# Power_Management.net
KiCad netlist of a schematic drawn in Altium Designer
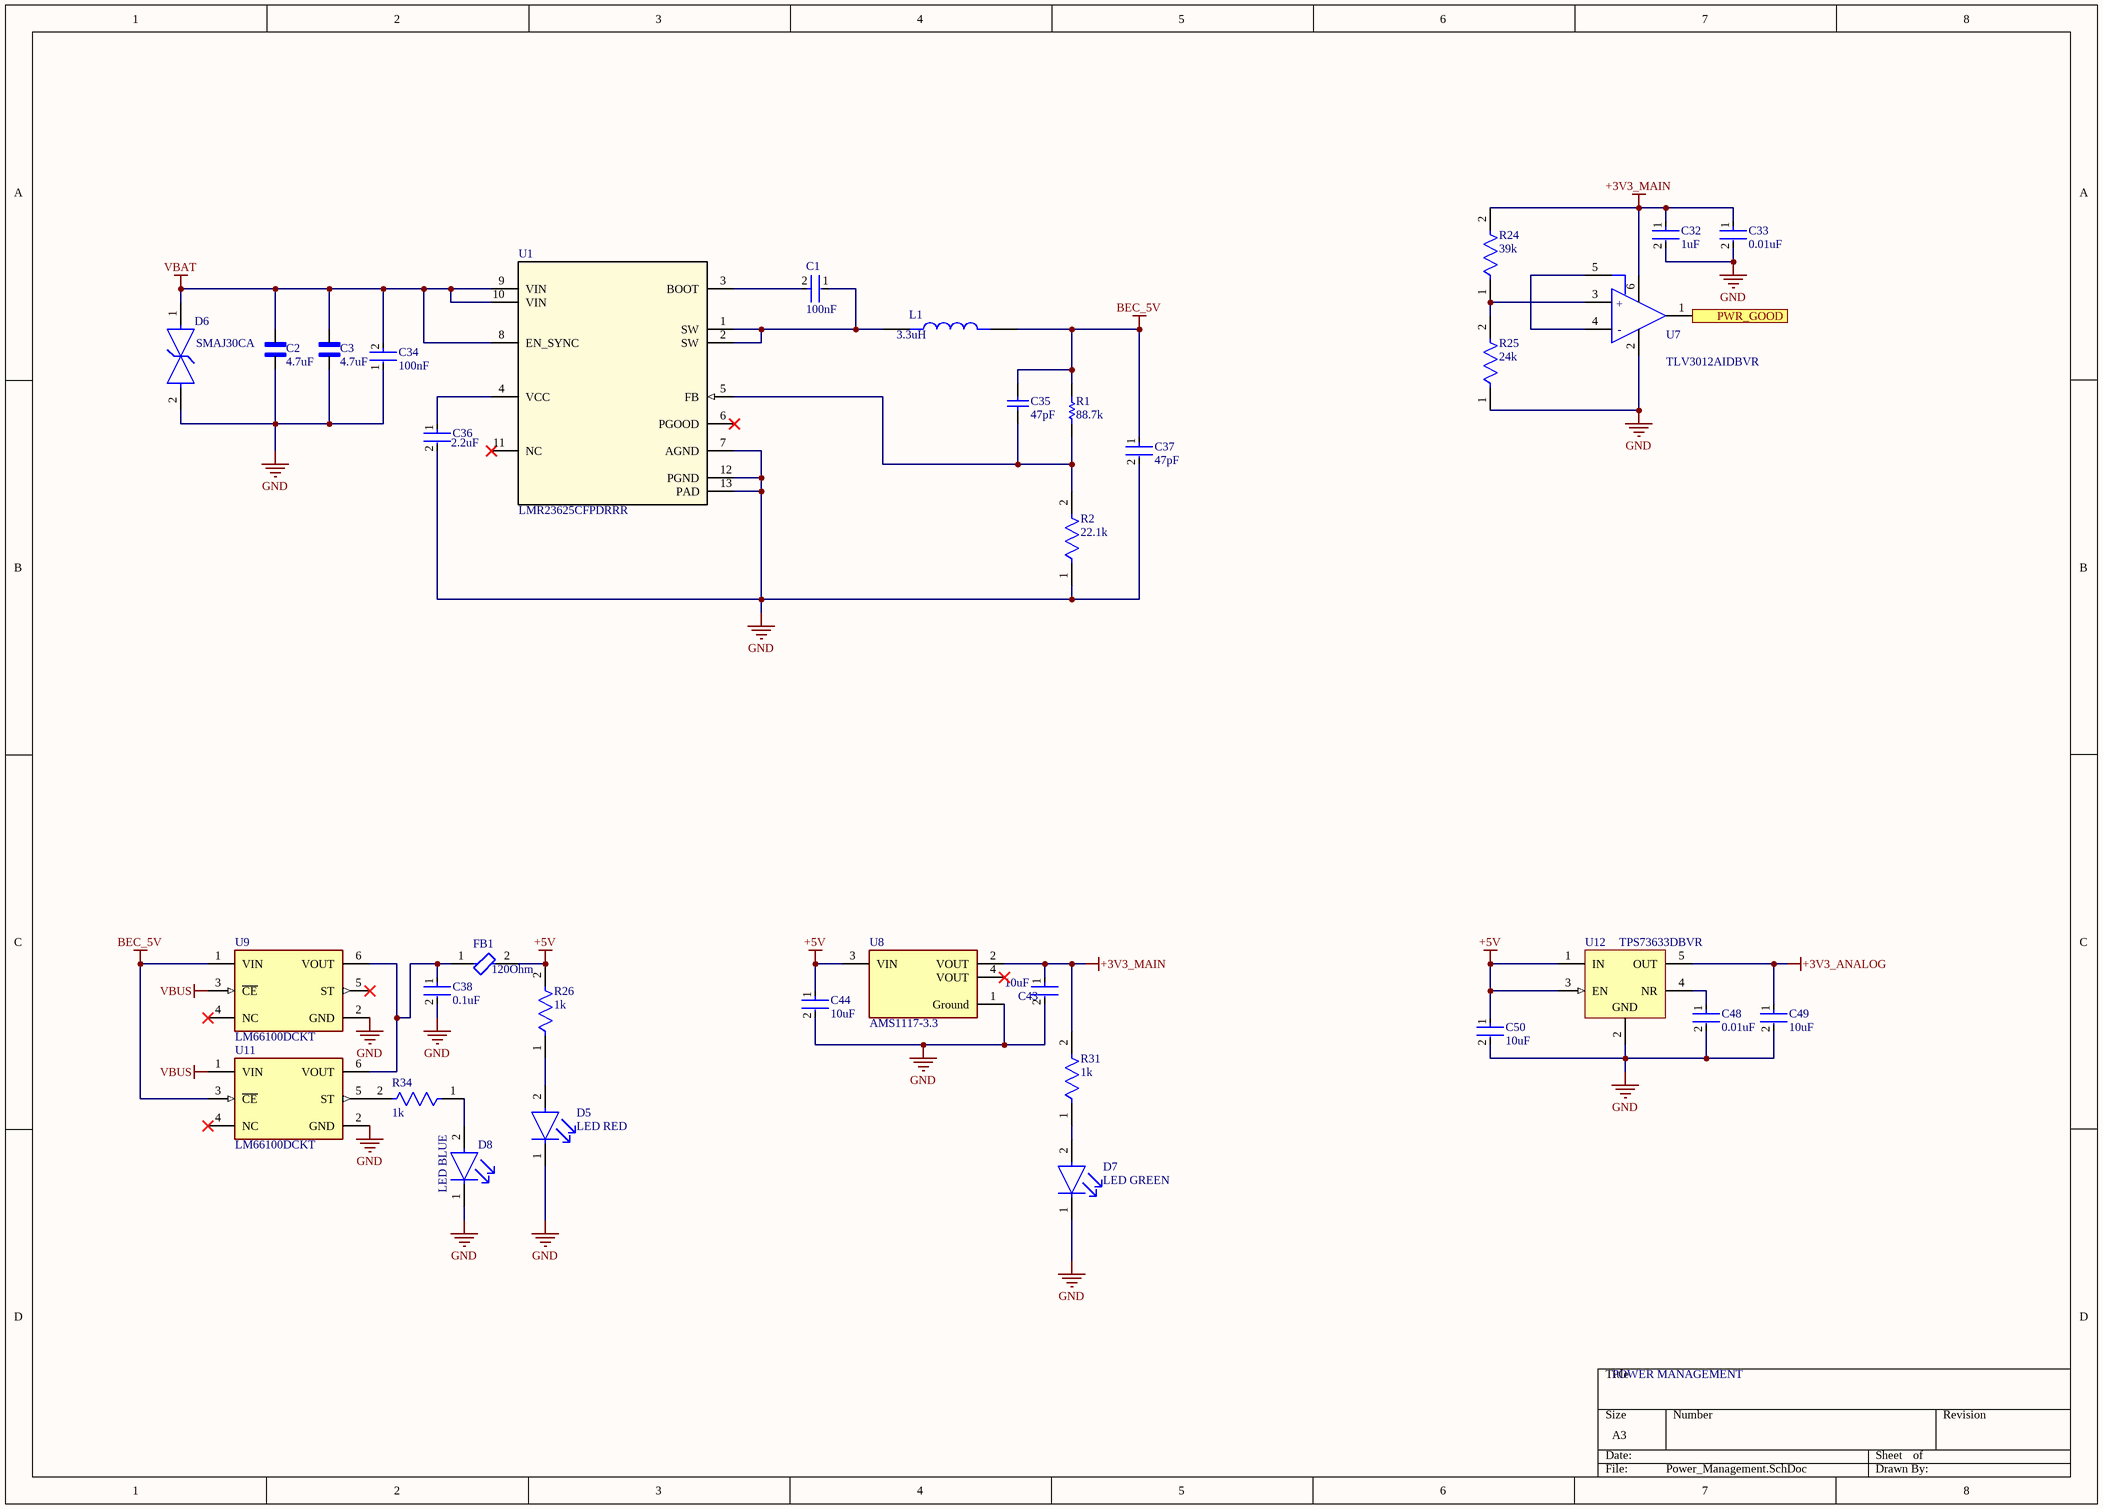
[diagram p0: Power_Management.SchDoc]

(export (version "E")
  (design (tool "Eeschema 10.0.6"))
  (components
    (comp (ref "C1")
      (value "100nF")
      (footprint "FP-GRM15-MFG")
      (description "CAP CER 0.1UF 16V X7R 0402")
      (fields (field (name "MANUFACTURER PART NUMBER") "GRM155R71C104KA88D") (field (name "TOLERANCE") "10%"))
      (libsource (lib "Altium Content Vault") (part "236180d848d6139a670b325ea6854c9"))
    )
    (comp (ref "C2")
      (value "4.7uF")
      (footprint "CAPC3225X270N")
      (fields
        (field (name "MF") "{'manufacturer': u'Taiyo Yuden'}")
        (field (name "MP") "MSASU32MSB7475MPNA01")
      )
      (libsource (lib "4.7uF CAP") (part "MSASU32MSB7475MPNA01"))
    )
    (comp (ref "C3")
      (value "4.7uF")
      (footprint "CAPC3225X270N")
      (fields
        (field (name "MF") "{'manufacturer': u'Taiyo Yuden'}")
        (field (name "MP") "MSASU32MSB7475MPNA01")
      )
      (libsource (lib "4.7uF CAP") (part "MSASU32MSB7475MPNA01"))
    )
    (comp (ref "C32")
      (value "1uF")
      (footprint "FP-GRM155-0_05-IPC_C")
      (description "Chip Multilayer Ceramic Capacitors for General Purpose, 0402, 1.0uF, B, 10%, 10%, 25V")
      (fields (field (name "TOLERANCE") "10%"))
      (libsource (lib "Altium Content Vault") (part "02cd4be3c70576c341d710602a673aa"))
    )
    (comp (ref "C33")
      (value "0.01uF")
      (footprint "FP-GRM022-0_02-IPC_B")
      (libsource (lib "Altium Content Vault") (part "b4654b650e69147ec39a6b967a45e02"))
    )
    (comp (ref "C34")
      (value "100nF")
      (footprint "FP-C1608-080-0_1-IPC_A")
      (description "Multilayer Ceramic Capacitors 100nF ±10% 100V X7S SMD 0603")
      (fields (field (name "TOLERANCE") "10%"))
      (libsource (lib "Altium Content Vault") (part "236180d848d6139a670b325ea6854c9"))
    )
    (comp (ref "C35")
      (value "47pF")
      (footprint "CAPC1005X55X25NL05T10")
      (fields (field (name "PART NUMBER") "GRM1555C1E470JA01D") (field (name "MANUFACTURER") "Murata"))
      (libsource (lib "Altium Content Vault") (part "CAP"))
    )
    (comp (ref "C36")
      (value "2.2uF")
      (footprint "FP-C1005-050-0_05-IPC_A")
      (description "Multilayer Ceramic Capacitors 2.2μF ±10% 16V X5R SMD 0402")
      (fields (field (name "TOLERANCE") "10%"))
      (libsource (lib "Altium Content Vault") (part "b4654b650e69147ec39a6b967a45e02"))
    )
    (comp (ref "C37")
      (value "47pF")
      (footprint "FP-GRM31C-0_2-e0_3_0_8-IPC_A")
      (description "Chip Multilayer Ceramic Capacitors for General Purpose, 1206, 47uF, X5R, 15%, 10%, 10V")
      (fields (field (name "TOLERANCE") "10%"))
      (libsource (lib "Altium Content Vault") (part "02cd4be3c70576c341d710602a673aa"))
    )
    (comp (ref "C38")
      (value "0.1uF")
      (footprint "FP-C0402-BB-MFG")
      (description "CAP CER 0.1UF 10V 20% X7R 0402")
      (fields
        (field (name "OCTOPART") "https://octopart.com/c0402c104m8ractu-kemet-9144037")
        (field (name "TOLERANCE") "0.2")
      )
      (libsource (lib "Altium Content Vault") (part "b4654b650e69147ec39a6b967a45e02"))
    )
    (comp (ref "C43")
      (value "10uF")
      (footprint "FP-C0402C106M9PACTU-MFG")
      (description "CAP CER 10UF 6.3V X5R 0402")
      (fields (field (name "TOLERANCE") "20%"))
      (libsource (lib "Altium Content Vault") (part "b4654b650e69147ec39a6b967a45e02"))
    )
    (comp (ref "C44")
      (value "10uF")
      (footprint "FP-C0402C106M9PACTU-MFG")
      (description "CAP CER 10UF 6.3V X5R 0402")
      (fields (field (name "TOLERANCE") "20%"))
      (libsource (lib "Altium Content Vault") (part "b4654b650e69147ec39a6b967a45e02"))
    )
    (comp (ref "C48")
      (value "0.01uF")
      (footprint "FP-GRM022-0_02-IPC_B")
      (libsource (lib "Altium Content Vault") (part "b4654b650e69147ec39a6b967a45e02"))
    )
    (comp (ref "C49")
      (value "10uF")
      (footprint "FP-C0402C106M9PACTU-MFG")
      (description "CAP CER 10UF 6.3V X5R 0402")
      (fields (field (name "TOLERANCE") "20%"))
      (libsource (lib "Altium Content Vault") (part "b4654b650e69147ec39a6b967a45e02"))
    )
    (comp (ref "C50")
      (value "10uF")
      (footprint "FP-C0402C106M9PACTU-MFG")
      (description "CAP CER 10UF 6.3V X5R 0402")
      (fields (field (name "TOLERANCE") "20%"))
      (libsource (lib "Altium Content Vault") (part "b4654b650e69147ec39a6b967a45e02"))
    )
    (comp (ref "D5")
      (value "LED RED")
      (footprint "FP-SML-LXT0805IW-TR-MFG")
      (description "LED RED DIFFUSED SMD")
      (libsource (lib "Altium Content Vault") (part "8706943c75ba83719d021d2fdc84c58"))
    )
    (comp (ref "D6")
      (value "SMAJ30CA")
      (footprint "FP-SMAJ-CA-MFG")
      (description "TVS DIODE 30V 48.4V DO214AC")
      (libsource (lib "Altium Content Vault") (part "876f4347bf90aa6f500f43e3cd03972"))
    )
    (comp (ref "D7")
      (value "LED GREEN")
      (footprint "FP-LTST-C171GKT-MFG")
      (description "LED GREEN CLEAR CHIP SMD")
      (libsource (lib "Altium Content Vault") (part "8706943c75ba83719d021d2fdc84c58"))
    )
    (comp (ref "D8")
      (value "LED BLUE")
      (footprint "FP-LTST-C191TBKT-MFG")
      (description "LED BLUE CLEAR CHIP SMD")
      (libsource (lib "Altium Content Vault") (part "8706943c75ba83719d021d2fdc84c58"))
    )
    (comp (ref "FB1")
      (value "120Ohm")
      (footprint "FP-BLM31-0_2-t1_1-MFG")
      (description "Chip Ferrite Bead Array, 1206, 120Ω @ 100MHz, 0.02Ω, 25%, 3.5A")
      (fields (field (name "TOLERANCE") "25%"))
      (libsource (lib "Altium Content Vault") (part "5f30dd21d616792df468990f7003faa"))
    )
    (comp (ref "L1")
      (value "3.3uH")
      (footprint "IND_XAL4030-332MEB")
      (fields (field (name "MP") "XAL4030-332MEB"))
      (libsource (lib "3.2uH") (part "XAL4030-332MEB"))
    )
    (comp (ref "R1")
      (value "88.7k")
      (footprint "RESC1005X40X25NL05T05")
      (fields (field (name "MANUFACTURER") "Vishay Dale") (field (name "PART NUMBER") "CRCW040288K7FKED"))
      (libsource (lib "Altium Content Vault") (part "RES"))
    )
    (comp (ref "R2")
      (value "22.1k")
      (footprint "FP-CRCW0402-e3-IPC_A")
      (description "RES Thick Film, 22.1kΩ, 1%, 0.063W, 100ppm/°C, 0402")
      (fields (field (name "TOLERANCE") "1%"))
      (libsource (lib "Altium Content Vault") (part "1029c3af85768c4190bb7ad29bc67b5"))
    )
    (comp (ref "R24")
      (value "39k")
      (footprint "FP-MCS0402-IPC_A")
      (description "RES SMD 1.2K OHM 1% 1/10W 0402")
      (fields (field (name "TOLERANCE") "0.1%"))
      (libsource (lib "Altium Content Vault") (part "1029c3af85768c4190bb7ad29bc67b5"))
    )
    (comp (ref "R25")
      (value "24k")
      (footprint "FP-CRCW0402-Pe3-IPC_C")
      (description "RES Thick Film, 24kΩ, 1%, 0.063W, 50ppm/°C, 0402")
      (fields (field (name "TOLERANCE") "1%"))
      (libsource (lib "Altium Content Vault") (part "1029c3af85768c4190bb7ad29bc67b5"))
    )
    (comp (ref "R26")
      (value "1k")
      (footprint "FP-MCS0402-IPC_A")
      (description "RES SMD 1.2K OHM 1% 1/10W 0402")
      (fields (field (name "TOLERANCE") "0.5%"))
      (libsource (lib "Altium Content Vault") (part "1029c3af85768c4190bb7ad29bc67b5"))
    )
    (comp (ref "R31")
      (value "1k")
      (footprint "FP-MCS0402-IPC_A")
      (description "RES SMD 1.2K OHM 1% 1/10W 0402")
      (fields (field (name "TOLERANCE") "0.5%"))
      (libsource (lib "Altium Content Vault") (part "1029c3af85768c4190bb7ad29bc67b5"))
    )
    (comp (ref "R34")
      (value "1k")
      (footprint "FP-MCS0402-IPC_A")
      (description "RES SMD 1.2K OHM 1% 1/10W 0402")
      (fields (field (name "TOLERANCE") "0.5%"))
      (libsource (lib "Altium Content Vault") (part "1029c3af85768c4190bb7ad29bc67b5"))
    )
    (comp (ref "U1")
      (value "LMR23625CFPDRRR")
      (footprint "DRR0012D")
      (description "SIMPLE SWITCHERÂ®, 36V 2.5A Synchronous Step-Down Converter 12-WSON -40 to 125")
      (fields (field (name "COPYRIGHT") "Copyright (C) 2025 Ultra Librarian. All rights reserved."))
      (libsource (lib "LMR23625CFPDRRR") (part "LMR23625CFPDRRR"))
    )
    (comp (ref "U7")
      (value "TLV3012AIDBVR")
      (footprint "FP-DBV0006A-IPC_B")
      (description "IC COMPARATOR 1.8V W/REF SOT23-6")
      (libsource (lib "Altium Content Vault") (part "c4a04de7fcb83ef995881f343e5bdea"))
    )
    (comp (ref "U8")
      (value "AMS1117-3.3")
      (footprint "FP-AMS1117-IPC_C")
      (description "LDO Voltage Regulators 1A, 3.3V")
      (fields
        (field (name "OCTOPART") "https://octopart.com/ams1117-3.3-advanced+monolithic+systems-25899300")
        (field (name "MANUFACTURER") "Advanced Monolithic Systems")
      )
      (libsource (lib "Altium Content Vault") (part "8bdbb5f8e77002000e30dd2845d0354"))
    )
    (comp (ref "U9")
      (value "LM66100DCKT")
      (footprint "FP-DCK0006A-MFG")
      (description "IC OR CTRLR IDEAL DIODE SC70-6")
      (libsource (lib "Altium Content Vault") (part "3595dc506fef48fc1df3095330a4feb"))
    )
    (comp (ref "U11")
      (value "LM66100DCKT")
      (footprint "FP-DCK0006A-MFG")
      (description "IC OR CTRLR IDEAL DIODE SC70-6")
      (libsource (lib "Altium Content Vault") (part "3595dc506fef48fc1df3095330a4feb"))
    )
    (comp (ref "U12")
      (value "TPS73633DBVR")
      (footprint "DBV0005A_L")
      (fields (field (name "MANUFACTURER") "Texas Instruments"))
      (libsource (lib "Altium Content Vault") (part "TI-TPS79NXX-YYSOT5"))
    )
  )
  (nets
    (net (code "1") (name "+3V3_ANALOG") (class "Default")
      (node (ref "C49") (pin "1") (pinfunction "1_1") (pintype "passive"))
      (node (ref "U12") (pin "5") (pinfunction "OUT_5") (pintype "power_in"))
    )
    (net (code "2") (name "+3V3_MAIN") (class "Default")
      (node (ref "C32") (pin "1") (pinfunction "1_1") (pintype "passive"))
      (node (ref "C33") (pin "1") (pinfunction "1_1") (pintype "passive"))
      (node (ref "C43") (pin "1") (pinfunction "1_1") (pintype "passive"))
      (node (ref "R24") (pin "2") (pinfunction "2_2") (pintype "passive"))
      (node (ref "R31") (pin "2") (pinfunction "2_2") (pintype "passive"))
      (node (ref "U7") (pin "6") (pinfunction "V+_6") (pintype "power_in"))
      (node (ref "U8") (pin "2") (pinfunction "VOUT_2") (pintype "passive"))
    )
    (net (code "3") (name "+5V") (class "Default")
      (node (ref "C44") (pin "1") (pinfunction "1_1") (pintype "passive"))
      (node (ref "C50") (pin "1") (pinfunction "1_1") (pintype "passive"))
      (node (ref "FB1") (pin "2") (pinfunction "2_2") (pintype "passive"))
      (node (ref "R26") (pin "2") (pinfunction "2_2") (pintype "passive"))
      (node (ref "U12") (pin "1") (pinfunction "IN_1") (pintype "power_in"))
      (node (ref "U12") (pin "3") (pinfunction "EN_3") (pintype "input"))
      (node (ref "U8") (pin "3") (pinfunction "VIN_3") (pintype "power_in"))
    )
    (net (code "4") (name "/PWR_GOOD") (class "Default")
      (node (ref "U7") (pin "1") (pinfunction "OUT_1") (pintype "passive"))
    )
    (net (code "5") (name "BEC_5V") (class "Default")
      (node (ref "C35") (pin "2") (pinfunction "2_2") (pintype "passive"))
      (node (ref "C37") (pin "1") (pinfunction "1_1") (pintype "passive"))
      (node (ref "L1") (pin "2") (pinfunction "2_2") (pintype "passive"))
      (node (ref "R1") (pin "2") (pinfunction "2_2") (pintype "passive"))
      (node (ref "U11") (pin "3") (pinfunction "~{CE}_3") (pintype "input"))
      (node (ref "U9") (pin "1") (pinfunction "VIN_1") (pintype "power_in"))
    )
    (net (code "6") (name "GND") (class "Default")
      (node (ref "C2") (pin "1") (pinfunction "1_1") (pintype "passive"))
      (node (ref "C3") (pin "1") (pinfunction "1_1") (pintype "passive"))
      (node (ref "C32") (pin "2") (pinfunction "2_2") (pintype "passive"))
      (node (ref "C33") (pin "2") (pinfunction "2_2") (pintype "passive"))
      (node (ref "C34") (pin "1") (pinfunction "1_1") (pintype "passive"))
      (node (ref "C36") (pin "2") (pinfunction "2_2") (pintype "passive"))
      (node (ref "C37") (pin "2") (pinfunction "2_2") (pintype "passive"))
      (node (ref "C38") (pin "2") (pinfunction "2_2") (pintype "passive"))
      (node (ref "C43") (pin "2") (pinfunction "2_2") (pintype "passive"))
      (node (ref "C44") (pin "2") (pinfunction "2_2") (pintype "passive"))
      (node (ref "C48") (pin "2") (pinfunction "2_2") (pintype "passive"))
      (node (ref "C49") (pin "2") (pinfunction "2_2") (pintype "passive"))
      (node (ref "C50") (pin "2") (pinfunction "2_2") (pintype "passive"))
      (node (ref "D5") (pin "1") (pinfunction "C_1") (pintype "passive"))
      (node (ref "D6") (pin "2") (pinfunction "2_2") (pintype "passive"))
      (node (ref "D7") (pin "1") (pinfunction "C_1") (pintype "passive"))
      (node (ref "D8") (pin "1") (pinfunction "C_1") (pintype "passive"))
      (node (ref "R2") (pin "1") (pinfunction "1_1") (pintype "passive"))
      (node (ref "R25") (pin "1") (pinfunction "1_1") (pintype "passive"))
      (node (ref "U1") (pin "12") (pinfunction "PGND_12") (pintype "power_in"))
      (node (ref "U1") (pin "13") (pinfunction "PAD_13") (pintype "power_in"))
      (node (ref "U1") (pin "7") (pinfunction "AGND_7") (pintype "power_in"))
      (node (ref "U11") (pin "2") (pinfunction "GND_2") (pintype "power_in"))
      (node (ref "U12") (pin "2") (pinfunction "GND_2") (pintype "power_in"))
      (node (ref "U7") (pin "2") (pinfunction "V-_2") (pintype "power_in"))
      (node (ref "U8") (pin "1") (pinfunction "Ground_1") (pintype "power_in"))
      (node (ref "U9") (pin "2") (pinfunction "GND_2") (pintype "power_in"))
    )
    (net (code "7") (name "Net-(C1-Pad1)") (class "Default")
      (node (ref "C1") (pin "1") (pinfunction "1_1") (pintype "passive"))
      (node (ref "L1") (pin "1") (pinfunction "1_1") (pintype "passive"))
      (node (ref "U1") (pin "1") (pinfunction "SW_1") (pintype "power_in"))
      (node (ref "U1") (pin "2") (pinfunction "SW_2") (pintype "power_in"))
    )
    (net (code "8") (name "Net-(D5-A)") (class "Default")
      (node (ref "D5") (pin "2") (pinfunction "A_2") (pintype "passive"))
      (node (ref "R26") (pin "1") (pinfunction "1_1") (pintype "passive"))
    )
    (net (code "9") (name "Net-(D7-A)") (class "Default")
      (node (ref "D7") (pin "2") (pinfunction "A_2") (pintype "passive"))
      (node (ref "R31") (pin "1") (pinfunction "1_1") (pintype "passive"))
    )
    (net (code "10") (name "Net-(D8-A)") (class "Default")
      (node (ref "D8") (pin "2") (pinfunction "A_2") (pintype "passive"))
      (node (ref "R34") (pin "1") (pinfunction "1_1") (pintype "passive"))
    )
    (net (code "11") (name "Net-(U1-BOOT)") (class "Default")
      (node (ref "C1") (pin "2") (pinfunction "2_2") (pintype "passive"))
      (node (ref "U1") (pin "3") (pinfunction "BOOT_3") (pintype "power_in"))
    )
    (net (code "12") (name "Net-(U1-FB)") (class "Default")
      (node (ref "C35") (pin "1") (pinfunction "1_1") (pintype "passive"))
      (node (ref "R1") (pin "1") (pinfunction "1_1") (pintype "passive"))
      (node (ref "R2") (pin "2") (pinfunction "2_2") (pintype "passive"))
      (node (ref "U1") (pin "5") (pinfunction "FB_5") (pintype "input"))
    )
    (net (code "13") (name "Net-(U1-VCC)") (class "Default")
      (node (ref "C36") (pin "1") (pinfunction "1_1") (pintype "passive"))
      (node (ref "U1") (pin "4") (pinfunction "VCC_4") (pintype "power_in"))
    )
    (net (code "14") (name "Net-(U7-IN+)") (class "Default")
      (node (ref "R24") (pin "1") (pinfunction "1_1") (pintype "passive"))
      (node (ref "R25") (pin "2") (pinfunction "2_2") (pintype "passive"))
      (node (ref "U7") (pin "3") (pinfunction "IN+_3") (pintype "tri_state"))
    )
    (net (code "15") (name "Net-(U7-IN-)") (class "Default")
      (node (ref "U7") (pin "4") (pinfunction "IN-_4") (pintype "tri_state"))
      (node (ref "U7") (pin "5") (pinfunction "REF_5") (pintype "passive"))
    )
    (net (code "16") (name "Net-(U11-ST)") (class "Default")
      (node (ref "R34") (pin "2") (pinfunction "2_2") (pintype "passive"))
      (node (ref "U11") (pin "5") (pinfunction "ST_5") (pintype "output"))
    )
    (net (code "17") (name "Net-(U11-VOUT)") (class "Default")
      (node (ref "C38") (pin "1") (pinfunction "1_1") (pintype "passive"))
      (node (ref "FB1") (pin "1") (pinfunction "1_1") (pintype "passive"))
      (node (ref "U11") (pin "6") (pinfunction "VOUT_6") (pintype "power_in"))
      (node (ref "U9") (pin "6") (pinfunction "VOUT_6") (pintype "power_in"))
    )
    (net (code "18") (name "Net-(U12-NR)") (class "Default")
      (node (ref "C48") (pin "1") (pinfunction "1_1") (pintype "passive"))
      (node (ref "U12") (pin "4") (pinfunction "NR_4") (pintype "passive"))
    )
    (net (code "19") (name "VBAT") (class "Default")
      (node (ref "C2") (pin "2") (pinfunction "2_2") (pintype "passive"))
      (node (ref "C3") (pin "2") (pinfunction "2_2") (pintype "passive"))
      (node (ref "C34") (pin "2") (pinfunction "2_2") (pintype "passive"))
      (node (ref "D6") (pin "1") (pinfunction "1_1") (pintype "passive"))
      (node (ref "U1") (pin "10") (pinfunction "VIN_10") (pintype "power_in"))
      (node (ref "U1") (pin "8") (pinfunction "EN_SYNC_8") (pintype "power_in"))
      (node (ref "U1") (pin "9") (pinfunction "VIN_9") (pintype "power_in"))
    )
    (net (code "20") (name "VBUS") (class "Default")
      (node (ref "U11") (pin "1") (pinfunction "VIN_1") (pintype "power_in"))
      (node (ref "U9") (pin "3") (pinfunction "~{CE}_3") (pintype "input"))
    )
    (net (code "21") (name "unconnected-(U1-NC-Pad11)") (class "Default")
      (node (ref "U1") (pin "11") (pinfunction "NC_11") (pintype "power_in+no_connect"))
    )
    (net (code "22") (name "unconnected-(U1-PGOOD-Pad6)") (class "Default")
      (node (ref "U1") (pin "6") (pinfunction "PGOOD_6") (pintype "passive+no_connect"))
    )
    (net (code "23") (name "unconnected-(U8-VOUT-Pad4)") (class "Default")
      (node (ref "U8") (pin "4") (pinfunction "VOUT_4") (pintype "passive+no_connect"))
    )
    (net (code "24") (name "unconnected-(U9-NC-Pad4)") (class "Default")
      (node (ref "U9") (pin "4") (pinfunction "NC_4") (pintype "passive+no_connect"))
    )
    (net (code "25") (name "unconnected-(U9-ST-Pad5)") (class "Default")
      (node (ref "U9") (pin "5") (pinfunction "ST_5") (pintype "output+no_connect"))
    )
    (net (code "26") (name "unconnected-(U11-NC-Pad4)") (class "Default")
      (node (ref "U11") (pin "4") (pinfunction "NC_4") (pintype "passive+no_connect"))
    )
  )
)
